# Buzzer_DIY_Kit.net
KiCad netlist of a schematic drawn in EasyEDA Pro
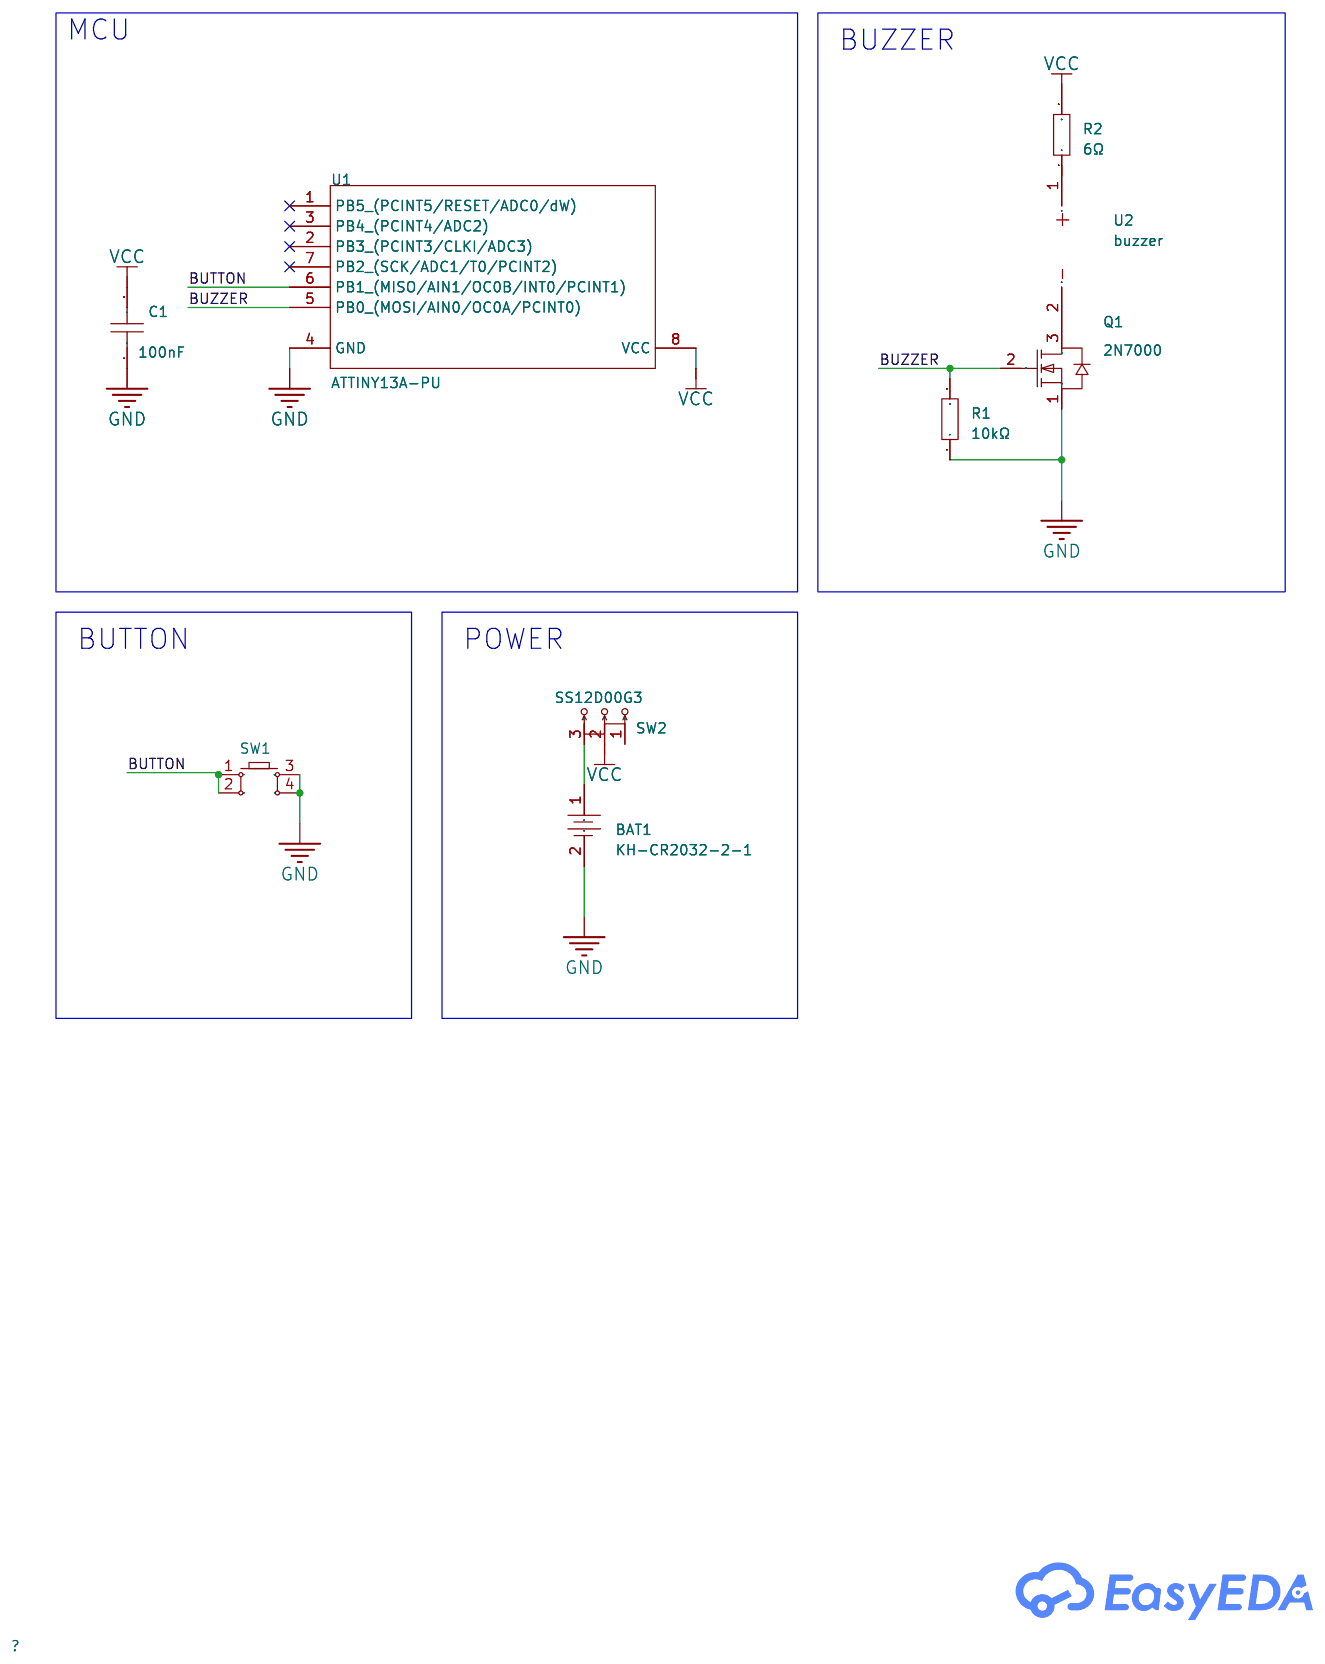
[diagram p0: schematic sheet]

(export (version "E")
  (design (tool "Eeschema 10.0.6"))
  (components
    (comp (ref "BAT1")
      (value "KH-CR2032-2-1")
      (footprint "easyedapro:BAT-TH_KH-CR2032-2-1")
      (fields (field (name "Manufacturer") "kinghelm(金航标)"))
      (libsource (lib "easyedapro") (part "KH-CR2032-2-1"))
    )
    (comp (ref "C1")
      (value "100nF")
      (footprint "easyedapro:CAP-TH_L4.8-W2.4-P5.08-D0.6")
      (fields
        (field (name "Manufacturer Part") "CC1H221KC1EDB44B1100")
        (field (name "Manufacturer") "Dersonic(德尔创)")
      )
      (libsource (lib "easyedapro") (part "CC1H221KC1EDB44B1100"))
    )
    (comp (ref "Q1")
      (value "2N7000")
      (footprint "easyedapro:TO-92-3_L4.9-W3.7-P1.27-L")
      (fields (field (name "Manufacturer") "onsemi(安森美)"))
      (libsource (lib "easyedapro") (part "2N7000_C232838"))
    )
    (comp (ref "R1")
      (value "10kΩ")
      (footprint "easyedapro:RES-TH_BD1.8-L3.2-P7.20-D0.4")
      (libsource (lib "easyedapro") (part "Res"))
    )
    (comp (ref "R2")
      (value "6Ω")
      (footprint "easyedapro:RES-TH_BD1.8-L3.2-P7.20-D0.4")
      (libsource (lib "easyedapro") (part "Res"))
    )
    (comp (ref "SW1")
      (value "~")
      (footprint "easyedapro:KEY-TH_4P-L6.0-W6.0-P3.90-LS6.5")
      (libsource (lib "easyedapro") (part "轻触按键"))
    )
    (comp (ref "SW2")
      (value "SS12D00G3")
      (footprint "easyedapro:SW-TH_SS-12D01-GX")
      (libsource (lib "easyedapro") (part "SS12D00G3"))
    )
    (comp (ref "U1")
      (value "ATTINY13A-PU")
      (footprint "easyedapro:DIP-8_L9.3-W6.4-P2.54-LS7.6-BL-1")
      (fields (field (name "Manufacturer") "MICROCHIP(美国微芯)"))
      (libsource (lib "easyedapro") (part "ATTINY13A-PU"))
    )
    (comp (ref "U2")
      (value "buzzer")
      (footprint "easyedapro:HC9042-03-CLDZ-ELECTROMAGNETIC PASSIVE INTEGRATED BUZZER-3V(9×4.2MM)")
      (libsource (lib "easyedapro") (part "buzzer"))
    )
  )
  (nets
    (net (code "1") (name "/BUTTON") (class "Default")
      (node (ref "SW1") (pin "1") (pinfunction "1_1") (pintype "input"))
      (node (ref "SW1") (pin "2") (pinfunction "2_2") (pintype "input"))
      (node (ref "U1") (pin "6") (pinfunction "PB1_(MISO/AIN1/OC0B/INT0/PCINT1)_6") (pintype "bidirectional"))
    )
    (net (code "2") (name "/BUZZER") (class "Default")
      (node (ref "Q1") (pin "2") (pinfunction "G_2") (pintype "unspecified"))
      (node (ref "R1") (pin "2") (pinfunction "2_2") (pintype "input"))
      (node (ref "U1") (pin "5") (pinfunction "PB0_(MOSI/AIN0/OC0A/PCINT0)_5") (pintype "bidirectional"))
    )
    (net (code "3") (name "GND") (class "Default")
      (node (ref "BAT1") (pin "2") (pinfunction "2_2") (pintype "input"))
      (node (ref "C1") (pin "1") (pinfunction "1_1") (pintype "unspecified"))
      (node (ref "Q1") (pin "1") (pinfunction "S_1") (pintype "unspecified"))
      (node (ref "R1") (pin "1") (pinfunction "1_1") (pintype "input"))
      (node (ref "SW1") (pin "3") (pinfunction "3_3") (pintype "input"))
      (node (ref "SW1") (pin "4") (pinfunction "4_4") (pintype "input"))
      (node (ref "U1") (pin "4") (pinfunction "GND_4") (pintype "unspecified"))
    )
    (net (code "4") (name "Net-(BAT1-Pad1)") (class "Default")
      (node (ref "BAT1") (pin "1") (pinfunction "1_1") (pintype "input"))
      (node (ref "SW2") (pin "3") (pinfunction "3_3") (pintype "unspecified"))
    )
    (net (code "5") (name "Net-(Q1-D)") (class "Default")
      (node (ref "Q1") (pin "3") (pinfunction "D_3") (pintype "unspecified"))
      (node (ref "U2") (pin "2") (pinfunction "2_2") (pintype "unspecified"))
    )
    (net (code "6") (name "Net-(R2-Pad1)") (class "Default")
      (node (ref "R2") (pin "1") (pinfunction "1_1") (pintype "input"))
      (node (ref "U2") (pin "1") (pinfunction "1_1") (pintype "unspecified"))
    )
    (net (code "7") (name "VCC") (class "Default")
      (node (ref "C1") (pin "2") (pinfunction "2_2") (pintype "unspecified"))
      (node (ref "R2") (pin "2") (pinfunction "2_2") (pintype "input"))
      (node (ref "SW2") (pin "2") (pinfunction "2_2") (pintype "unspecified"))
      (node (ref "U1") (pin "8") (pinfunction "VCC_8") (pintype "unspecified"))
    )
    (net (code "8") (name "unconnected-(SW2-Pad1)") (class "Default")
      (node (ref "SW2") (pin "1") (pinfunction "1_1") (pintype "unspecified"))
    )
    (net (code "9") (name "unconnected-(U1-PB2_(SCK{slash}ADC1{slash}T0{slash}PCINT2)-Pad7)") (class "Default")
      (node (ref "U1") (pin "7") (pinfunction "PB2_(SCK/ADC1/T0/PCINT2)_7") (pintype "bidirectional+no_connect"))
    )
    (net (code "10") (name "unconnected-(U1-PB3_(PCINT3{slash}CLKI{slash}ADC3)-Pad2)") (class "Default")
      (node (ref "U1") (pin "2") (pinfunction "PB3_(PCINT3/CLKI/ADC3)_2") (pintype "bidirectional+no_connect"))
    )
    (net (code "11") (name "unconnected-(U1-PB4_(PCINT4{slash}ADC2)-Pad3)") (class "Default")
      (node (ref "U1") (pin "3") (pinfunction "PB4_(PCINT4/ADC2)_3") (pintype "bidirectional+no_connect"))
    )
    (net (code "12") (name "unconnected-(U1-PB5_(PCINT5{slash}RESET{slash}ADC0{slash}dW)-Pad1)") (class "Default")
      (node (ref "U1") (pin "1") (pinfunction "PB5_(PCINT5/RESET/ADC0/dW)_1") (pintype "bidirectional+no_connect"))
    )
  )
)
